# lm3410-sepic-led-driver-16mm-mk-3-led.net
KiCad netlist of a schematic drawn in EAGLE
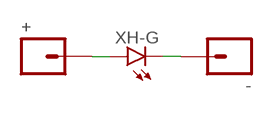
[diagram p0: schematic, sheet 1]

(export (version "E")
  (design (tool "Eeschema 10.0.6"))
  (components
    (comp (ref "+")
      (value "M01PTH-1.2MM")
      (footprint "eagle-import:1X01-1.2MM")
      (libsource (lib "eagle-import") (part "M01PTH-1.2MM"))
    )
    (comp (ref "-")
      (value "M01PTH-1.2MM-NS")
      (footprint "eagle-import:1X01-1.2MM-NS")
      (libsource (lib "eagle-import") (part "M01PTH-1.2MM-NS"))
    )
    (comp (ref "XH-G")
      (value "LEDBIG-ASS-RED-LED")
      (footprint "eagle-import:LED-GULL-WINGS-MINE-MINE-MINE")
      (libsource (lib "eagle-import") (part "LEDBIG-ASS-RED-LED"))
    )
  )
  (nets
    (net (code "1") (name "Net-(+-1)") (class "Default")
      (node (ref "+") (pin "P$1") (pinfunction "1_P$1") (pintype "passive"))
      (node (ref "XH-G") (pin "A") (pinfunction "A_A") (pintype "passive"))
    )
    (net (code "2") (name "Net-(--1)") (class "Default")
      (node (ref "-") (pin "P$1") (pinfunction "1_P$1") (pintype "passive"))
      (node (ref "XH-G") (pin "K") (pinfunction "C_K") (pintype "passive"))
      (node (ref "XH-G") (pin "K@1") (pinfunction "C_K@1") (pintype "passive"))
      (node (ref "XH-G") (pin "K@10") (pinfunction "C_K@10") (pintype "passive"))
      (node (ref "XH-G") (pin "K@11") (pinfunction "C_K@11") (pintype "passive"))
      (node (ref "XH-G") (pin "K@12") (pinfunction "C_K@12") (pintype "passive"))
      (node (ref "XH-G") (pin "K@13") (pinfunction "C_K@13") (pintype "passive"))
      (node (ref "XH-G") (pin "K@14") (pinfunction "C_K@14") (pintype "passive"))
      (node (ref "XH-G") (pin "K@15") (pinfunction "C_K@15") (pintype "passive"))
      (node (ref "XH-G") (pin "K@16") (pinfunction "C_K@16") (pintype "passive"))
      (node (ref "XH-G") (pin "K@17") (pinfunction "C_K@17") (pintype "passive"))
      (node (ref "XH-G") (pin "K@18") (pinfunction "C_K@18") (pintype "passive"))
      (node (ref "XH-G") (pin "K@19") (pinfunction "C_K@19") (pintype "passive"))
      (node (ref "XH-G") (pin "K@20") (pinfunction "C_K@20") (pintype "passive"))
      (node (ref "XH-G") (pin "K@21") (pinfunction "C_K@21") (pintype "passive"))
      (node (ref "XH-G") (pin "K@23") (pinfunction "C_K@23") (pintype "passive"))
      (node (ref "XH-G") (pin "K@24") (pinfunction "C_K@24") (pintype "passive"))
      (node (ref "XH-G") (pin "K@25") (pinfunction "C_K@25") (pintype "passive"))
      (node (ref "XH-G") (pin "K@3") (pinfunction "C_K@3") (pintype "passive"))
      (node (ref "XH-G") (pin "K@4") (pinfunction "C_K@4") (pintype "passive"))
      (node (ref "XH-G") (pin "K@5") (pinfunction "C_K@5") (pintype "passive"))
      (node (ref "XH-G") (pin "K@7") (pinfunction "C_K@7") (pintype "passive"))
      (node (ref "XH-G") (pin "K@8") (pinfunction "C_K@8") (pintype "passive"))
      (node (ref "XH-G") (pin "K@9") (pinfunction "C_K@9") (pintype "passive"))
    )
  )
)
